# Motor_Breakout.net
KiCad netlist of a schematic drawn in Altium Designer
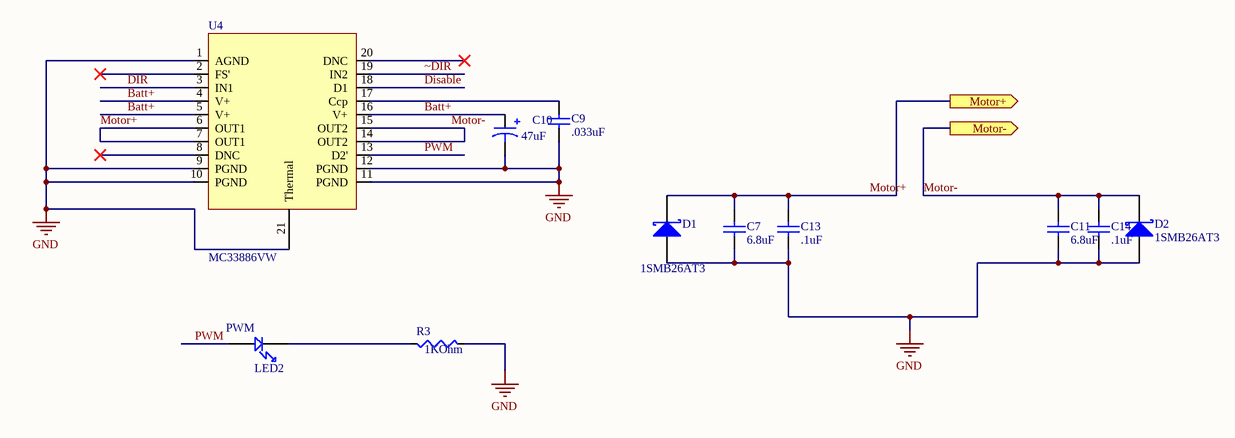
[diagram p0: Motor_Breakout.SchDoc]

(export (version "E")
  (design (tool "Eeschema 10.0.6"))
  (components
    (comp (ref "C7")
      (value "6.8uF")
      (footprint "R 1210 (3225) RESISTOR")
      (description "Capacitor")
      (libsource (lib "PassiveComponents") (part "Capacitor (non-polarized)"))
    )
    (comp (ref "C9")
      (value ".033uF")
      (footprint "0805 (2012) Capacitor")
      (description "Capacitor")
      (libsource (lib "PassiveComponents") (part "Capacitor (non-polarized)"))
    )
    (comp (ref "C10")
      (value "47uF")
      (footprint "Radial_6.3mmDia_SM_D")
      (description "Capacitor (polarized)")
      (libsource (lib "PassiveComponents") (part "Capacitor (polarized)"))
    )
    (comp (ref "C11")
      (value "6.8uF")
      (footprint "R 1210 (3225) RESISTOR")
      (description "Capacitor")
      (libsource (lib "PassiveComponents") (part "Capacitor (non-polarized)"))
    )
    (comp (ref "C13")
      (value ".1uF")
      (footprint "0805 (2012) Capacitor")
      (description "Capacitor")
      (libsource (lib "PassiveComponents") (part "Capacitor (non-polarized)"))
    )
    (comp (ref "C14")
      (value ".1uF")
      (footprint "0805 (2012) Capacitor")
      (description "Capacitor")
      (libsource (lib "PassiveComponents") (part "Capacitor (non-polarized)"))
    )
    (comp (ref "D1")
      (value "1SMB26AT3")
      (footprint "SMB")
      (description "Schottky Diode")
      (fields (field (name "PUBLISHER") "Altium Limited"))
      (libsource (lib "Miscellaneous Devices") (part "D Schottky"))
    )
    (comp (ref "D2")
      (value "1SMB26AT3")
      (footprint "SMB")
      (description "Schottky Diode")
      (fields (field (name "PUBLISHER") "Altium Limited"))
      (libsource (lib "Miscellaneous Devices") (part "D Schottky"))
    )
    (comp (ref "LED2")
      (value "PWM")
      (footprint "LED 0805")
      (description "Standard LED")
      (libsource (lib "PassiveComponents") (part "LED"))
    )
    (comp (ref "R3")
      (value "1KOhm")
      (footprint "R 0805 (2012) RESISTOR")
      (description "Resistor")
      (libsource (lib "PassiveComponents") (part "Resistor"))
    )
    (comp (ref "U4")
      (value "MC33886VW")
      (footprint "SOP127P1420X340_HS-20N")
      (description "Motor Controller")
      (libsource (lib "Kanaloa_v2.0.0_Motor") (part "MC33886VW"))
    )
  )
  (nets
    (net (code "1") (name "/Batt+") (class "Default")
      (node (ref "C10") (pin "P") (pinfunction "1_P") (pintype "passive"))
      (node (ref "U4") (pin "16") (pinfunction "V+_16") (pintype "passive"))
      (node (ref "U4") (pin "4") (pinfunction "V+_4") (pintype "passive"))
      (node (ref "U4") (pin "5") (pinfunction "V+_5") (pintype "passive"))
    )
    (net (code "2") (name "/DIR") (class "Default")
      (node (ref "U4") (pin "3") (pinfunction "IN1_3") (pintype "passive"))
    )
    (net (code "3") (name "/Disable") (class "Default")
      (node (ref "U4") (pin "18") (pinfunction "D1_18") (pintype "passive"))
    )
    (net (code "4") (name "/Motor+") (class "Default")
      (node (ref "C13") (pin "2") (pinfunction "2_2") (pintype "passive"))
      (node (ref "C7") (pin "2") (pinfunction "2_2") (pintype "passive"))
      (node (ref "D1") (pin "2") (pinfunction "K_2") (pintype "passive"))
      (node (ref "U4") (pin "6") (pinfunction "OUT1_6") (pintype "passive"))
      (node (ref "U4") (pin "7") (pinfunction "OUT1_7") (pintype "passive"))
    )
    (net (code "5") (name "/Motor-") (class "Default")
      (node (ref "C11") (pin "2") (pinfunction "2_2") (pintype "passive"))
      (node (ref "C14") (pin "2") (pinfunction "2_2") (pintype "passive"))
      (node (ref "D2") (pin "2") (pinfunction "K_2") (pintype "passive"))
      (node (ref "U4") (pin "14") (pinfunction "OUT2_14") (pintype "passive"))
      (node (ref "U4") (pin "15") (pinfunction "OUT2_15") (pintype "passive"))
    )
    (net (code "6") (name "/PWM") (class "Default")
      (node (ref "LED2") (pin "2") (pinfunction "2_2") (pintype "passive"))
      (node (ref "U4") (pin "13") (pinfunction "D2'_13") (pintype "passive"))
    )
    (net (code "7") (name "/~DIR") (class "Default")
      (node (ref "U4") (pin "19") (pinfunction "IN2_19") (pintype "passive"))
    )
    (net (code "8") (name "GND") (class "Default")
      (node (ref "C10") (pin "N") (pinfunction "2_N") (pintype "passive"))
      (node (ref "C11") (pin "1") (pinfunction "1_1") (pintype "passive"))
      (node (ref "C13") (pin "1") (pinfunction "1_1") (pintype "passive"))
      (node (ref "C14") (pin "1") (pinfunction "1_1") (pintype "passive"))
      (node (ref "C7") (pin "1") (pinfunction "1_1") (pintype "passive"))
      (node (ref "C9") (pin "1") (pinfunction "1_1") (pintype "passive"))
      (node (ref "D1") (pin "1") (pinfunction "A_1") (pintype "passive"))
      (node (ref "D2") (pin "1") (pinfunction "A_1") (pintype "passive"))
      (node (ref "R3") (pin "2") (pinfunction "2_2") (pintype "passive"))
      (node (ref "U4") (pin "1") (pinfunction "AGND_1") (pintype "passive"))
      (node (ref "U4") (pin "10") (pinfunction "PGND_10") (pintype "passive"))
      (node (ref "U4") (pin "11") (pinfunction "PGND_11") (pintype "passive"))
      (node (ref "U4") (pin "12") (pinfunction "PGND_12") (pintype "passive"))
      (node (ref "U4") (pin "21") (pinfunction "Thermal_21") (pintype "passive"))
      (node (ref "U4") (pin "9") (pinfunction "PGND_9") (pintype "passive"))
    )
    (net (code "9") (name "Net-(LED2-Pad1)") (class "Default")
      (node (ref "LED2") (pin "1") (pinfunction "1_1") (pintype "passive"))
      (node (ref "R3") (pin "1") (pinfunction "1_1") (pintype "passive"))
    )
    (net (code "10") (name "Net-(U4-Ccp)") (class "Default")
      (node (ref "C9") (pin "2") (pinfunction "2_2") (pintype "passive"))
      (node (ref "U4") (pin "17") (pinfunction "Ccp_17") (pintype "passive"))
    )
    (net (code "11") (name "unconnected-(U4-DNC-Pad8)") (class "Default")
      (node (ref "U4") (pin "8") (pinfunction "DNC_8") (pintype "passive+no_connect"))
    )
    (net (code "12") (name "unconnected-(U4-DNC-Pad20)") (class "Default")
      (node (ref "U4") (pin "20") (pinfunction "DNC_20") (pintype "passive+no_connect"))
    )
    (net (code "13") (name "unconnected-(U4-FS'-Pad2)") (class "Default")
      (node (ref "U4") (pin "2") (pinfunction "FS'_2") (pintype "passive+no_connect"))
    )
  )
)
